# Communicate_module.net
KiCad netlist of a schematic drawn in Altium Designer
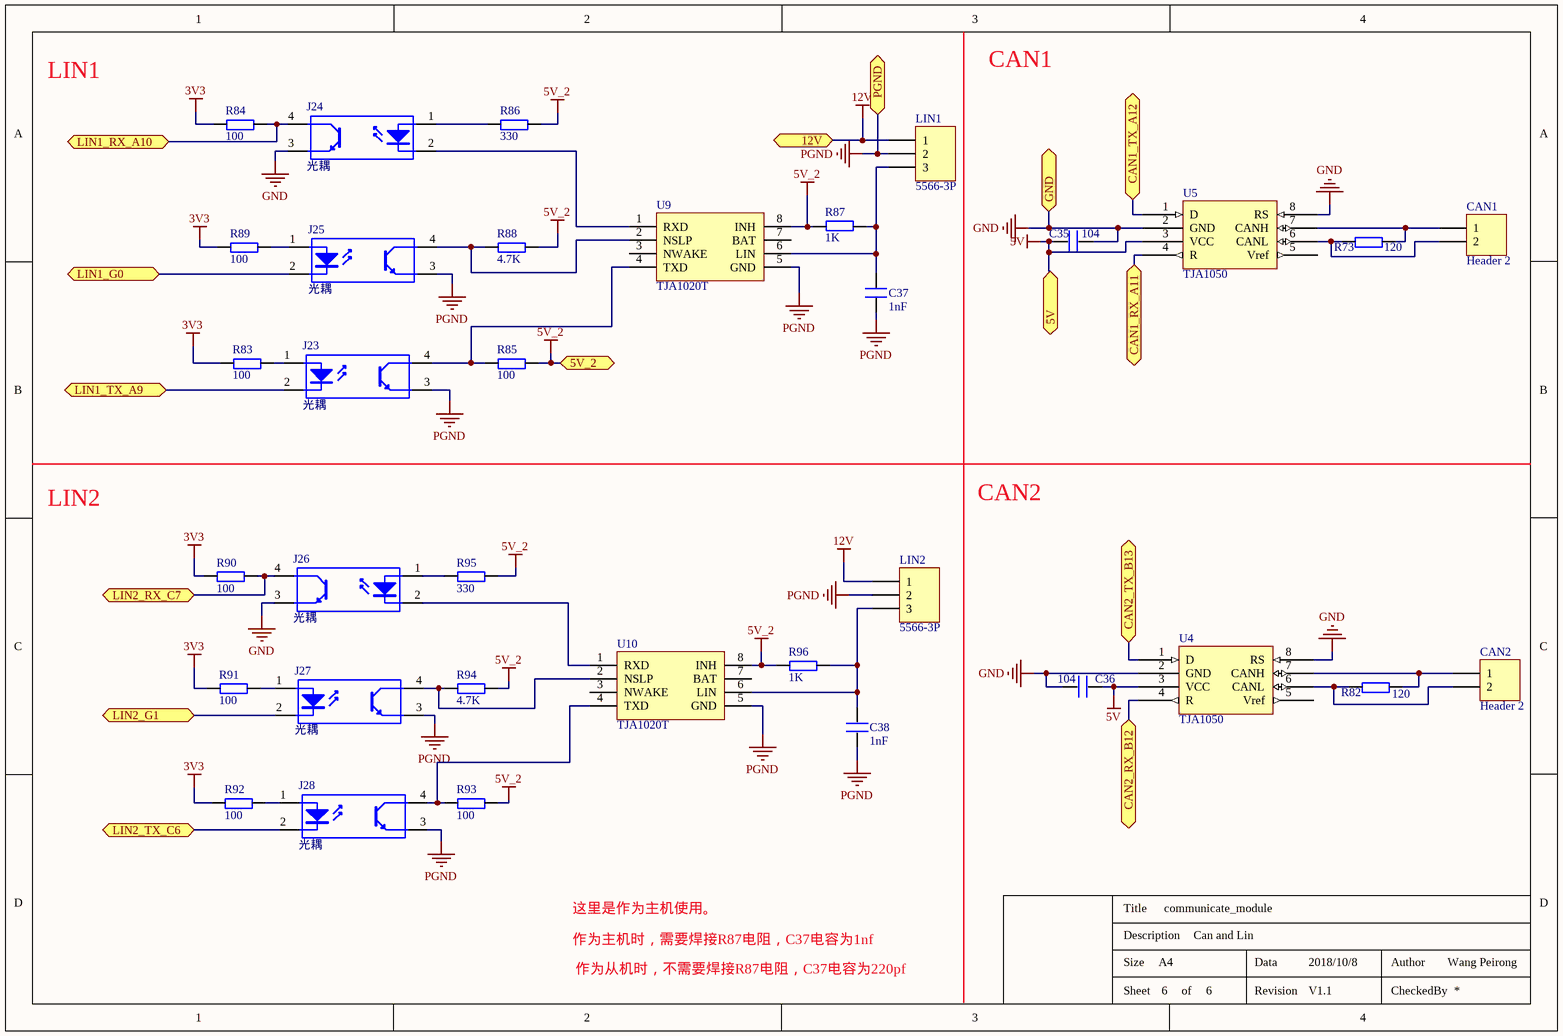
[diagram p0: Communicate_module.SchDoc]

(export (version "E")
  (design (tool "Eeschema 10.0.6"))
  (components
    (comp (ref "C35") (value "104") (footprint "0603P") (libsource (lib "阿波罗STM32F4&F7底板封装库") (part "C")))
    (comp (ref "C36") (value "104") (footprint "0603P") (libsource (lib "阿波罗STM32F4&F7底板封装库") (part "C")))
    (comp (ref "C37") (value "1nF") (footprint "0603P") (libsource (lib "阿波罗STM32F4&F7底板封装库") (part "C")))
    (comp (ref "C38") (value "1nF") (footprint "0603P") (libsource (lib "阿波罗STM32F4&F7底板封装库") (part "C")))
    (comp (ref "CAN1")
      (value "Header 2")
      (footprint "5566-2P")
      (description "Header, 2-Pin")
      (fields (field (name "PUBLISHER") "Altium Limited"))
      (libsource (lib "接插件集成库") (part "Header 2"))
    )
    (comp (ref "CAN2")
      (value "Header 2")
      (footprint "5566-2P")
      (description "Header, 2-Pin")
      (fields (field (name "PUBLISHER") "Altium Limited"))
      (libsource (lib "接插件集成库") (part "Header 2"))
    )
    (comp (ref "J23")
      (value "光耦")
      (footprint "SOP127P710X350-4N")
      (fields (field (name "PUBLISHER") "Altium Limited"))
      (libsource (lib "常用元件集成库") (part "光耦"))
    )
    (comp (ref "J24")
      (value "光耦")
      (footprint "SOP127P710X350-4N")
      (fields (field (name "PUBLISHER") "Altium Limited"))
      (libsource (lib "常用元件集成库") (part "光耦"))
    )
    (comp (ref "J25")
      (value "光耦")
      (footprint "SOP127P710X350-4N")
      (fields (field (name "PUBLISHER") "Altium Limited"))
      (libsource (lib "常用元件集成库") (part "光耦"))
    )
    (comp (ref "J26")
      (value "光耦")
      (footprint "SOP127P710X350-4N")
      (fields (field (name "PUBLISHER") "Altium Limited"))
      (libsource (lib "常用元件集成库") (part "光耦"))
    )
    (comp (ref "J27")
      (value "光耦")
      (footprint "SOP127P710X350-4N")
      (fields (field (name "PUBLISHER") "Altium Limited"))
      (libsource (lib "常用元件集成库") (part "光耦"))
    )
    (comp (ref "J28")
      (value "光耦")
      (footprint "SOP127P710X350-4N")
      (fields (field (name "PUBLISHER") "Altium Limited"))
      (libsource (lib "常用元件集成库") (part "光耦"))
    )
    (comp (ref "LIN1")
      (value "5566-3P")
      (footprint "5566-3P")
      (description "Header, 3-Pin")
      (fields (field (name "PUBLISHER") "Altium Limited"))
      (libsource (lib "接插件集成库") (part "Header 3"))
    )
    (comp (ref "LIN2")
      (value "5566-3P")
      (footprint "5566-3P")
      (description "Header, 3-Pin")
      (fields (field (name "PUBLISHER") "Altium Limited"))
      (libsource (lib "接插件集成库") (part "Header 3"))
    )
    (comp (ref "R73") (value "120") (footprint "0603P") (libsource (lib "阿波罗STM32F4&F7底板封装库") (part "R")))
    (comp (ref "R82") (value "120") (footprint "0603P") (libsource (lib "阿波罗STM32F4&F7底板封装库") (part "R")))
    (comp (ref "R83") (value "100") (footprint "0603P") (libsource (lib "阿波罗STM32F4&F7底板封装库") (part "R")))
    (comp (ref "R84") (value "100") (footprint "0603P") (libsource (lib "阿波罗STM32F4&F7底板封装库") (part "R")))
    (comp (ref "R85") (value "100") (footprint "0603P") (libsource (lib "阿波罗STM32F4&F7底板封装库") (part "R")))
    (comp (ref "R86") (value "330") (footprint "0603P") (libsource (lib "阿波罗STM32F4&F7底板封装库") (part "R")))
    (comp (ref "R87") (value "1K") (footprint "0603P") (libsource (lib "阿波罗STM32F4&F7底板封装库") (part "R")))
    (comp (ref "R88") (value "4.7K") (footprint "0603P") (libsource (lib "阿波罗STM32F4&F7底板封装库") (part "R")))
    (comp (ref "R89") (value "100") (footprint "0603P") (libsource (lib "阿波罗STM32F4&F7底板封装库") (part "R")))
    (comp (ref "R90") (value "100") (footprint "0603P") (libsource (lib "阿波罗STM32F4&F7底板封装库") (part "R")))
    (comp (ref "R91") (value "100") (footprint "0603P") (libsource (lib "阿波罗STM32F4&F7底板封装库") (part "R")))
    (comp (ref "R92") (value "100") (footprint "0603P") (libsource (lib "阿波罗STM32F4&F7底板封装库") (part "R")))
    (comp (ref "R93") (value "100") (footprint "0603P") (libsource (lib "阿波罗STM32F4&F7底板封装库") (part "R")))
    (comp (ref "R94") (value "4.7K") (footprint "0603P") (libsource (lib "阿波罗STM32F4&F7底板封装库") (part "R")))
    (comp (ref "R95") (value "330") (footprint "0603P") (libsource (lib "阿波罗STM32F4&F7底板封装库") (part "R")))
    (comp (ref "R96") (value "1K") (footprint "0603P") (libsource (lib "阿波罗STM32F4&F7底板封装库") (part "R")))
    (comp (ref "U4")
      (value "TJA1050")
      (footprint "SOP-8")
      (libsource (lib "阿波罗STM32F4&F7底板封装库") (part "SN65HVD230D"))
    )
    (comp (ref "U5")
      (value "TJA1050")
      (footprint "SOP-8")
      (libsource (lib "阿波罗STM32F4&F7底板封装库") (part "SN65HVD230D"))
    )
    (comp (ref "U9") (value "TJA1020T") (footprint "NSO8_N") (libsource (lib "IC集成库") (part "TJA1020T")))
    (comp (ref "U10") (value "TJA1020T") (footprint "NSO8_N") (libsource (lib "IC集成库") (part "TJA1020T")))
  )
  (nets
    (net (code "1") (name "/CAN1_RX_A11") (class "Default")
      (node (ref "U5") (pin "4") (pinfunction "R_4") (pintype "output"))
    )
    (net (code "2") (name "/CAN1_TX_A12") (class "Default")
      (node (ref "U5") (pin "1") (pinfunction "D_1") (pintype "input"))
    )
    (net (code "3") (name "/CAN2_RX_B12") (class "Default")
      (node (ref "U4") (pin "4") (pinfunction "R_4") (pintype "output"))
    )
    (net (code "4") (name "/CAN2_TX_B13") (class "Default")
      (node (ref "U4") (pin "1") (pinfunction "D_1") (pintype "input"))
    )
    (net (code "5") (name "/LIN1_G0") (class "Default")
      (node (ref "J25") (pin "2") (pinfunction "K_2") (pintype "passive"))
    )
    (net (code "6") (name "/LIN1_RX_A10") (class "Default")
      (node (ref "J24") (pin "4") (pinfunction "C_4") (pintype "passive"))
      (node (ref "R84") (pin "2") (pintype "passive"))
    )
    (net (code "7") (name "/LIN1_TX_A9") (class "Default")
      (node (ref "J23") (pin "2") (pinfunction "K_2") (pintype "passive"))
    )
    (net (code "8") (name "/LIN2_G1") (class "Default")
      (node (ref "J27") (pin "2") (pinfunction "K_2") (pintype "passive"))
    )
    (net (code "9") (name "/LIN2_RX_C7") (class "Default")
      (node (ref "J26") (pin "4") (pinfunction "C_4") (pintype "passive"))
      (node (ref "R90") (pin "2") (pintype "passive"))
    )
    (net (code "10") (name "/LIN2_TX_C6") (class "Default")
      (node (ref "J28") (pin "2") (pinfunction "K_2") (pintype "passive"))
    )
    (net (code "11") (name "3V3") (class "Default")
      (node (ref "R83") (pin "1") (pintype "passive"))
      (node (ref "R84") (pin "1") (pintype "passive"))
      (node (ref "R89") (pin "1") (pintype "passive"))
      (node (ref "R90") (pin "1") (pintype "passive"))
      (node (ref "R91") (pin "1") (pintype "passive"))
      (node (ref "R92") (pin "1") (pintype "passive"))
    )
    (net (code "12") (name "5V") (class "Default")
      (node (ref "C35") (pin "1") (pintype "passive"))
      (node (ref "C36") (pin "2") (pintype "passive"))
      (node (ref "U4") (pin "3") (pinfunction "VCC_3") (pintype "power_in"))
      (node (ref "U5") (pin "3") (pinfunction "VCC_3") (pintype "power_in"))
    )
    (net (code "13") (name "5V_2") (class "Default")
      (node (ref "R85") (pin "2") (pintype "passive"))
      (node (ref "R86") (pin "2") (pintype "passive"))
      (node (ref "R87") (pin "2") (pintype "passive"))
      (node (ref "R88") (pin "2") (pintype "passive"))
      (node (ref "R93") (pin "2") (pintype "passive"))
      (node (ref "R94") (pin "2") (pintype "passive"))
      (node (ref "R95") (pin "2") (pintype "passive"))
      (node (ref "R96") (pin "1") (pintype "passive"))
      (node (ref "U10") (pin "8") (pinfunction "INH_8") (pintype "passive"))
      (node (ref "U9") (pin "8") (pinfunction "INH_8") (pintype "passive"))
    )
    (net (code "14") (name "12V") (class "Default")
      (node (ref "LIN1") (pin "1") (pinfunction "1_1") (pintype "passive"))
      (node (ref "LIN2") (pin "1") (pinfunction "1_1") (pintype "passive"))
    )
    (net (code "15") (name "GND") (class "Default")
      (node (ref "C35") (pin "2") (pintype "passive"))
      (node (ref "C36") (pin "1") (pintype "passive"))
      (node (ref "J24") (pin "3") (pinfunction "E_3") (pintype "passive"))
      (node (ref "J26") (pin "3") (pinfunction "E_3") (pintype "passive"))
      (node (ref "U4") (pin "2") (pinfunction "GND_2") (pintype "power_in"))
      (node (ref "U4") (pin "8") (pinfunction "RS_8") (pintype "input"))
      (node (ref "U5") (pin "2") (pinfunction "GND_2") (pintype "power_in"))
      (node (ref "U5") (pin "8") (pinfunction "RS_8") (pintype "input"))
    )
    (net (code "16") (name "Net-(J23-A)") (class "Default")
      (node (ref "J23") (pin "1") (pinfunction "A_1") (pintype "passive"))
      (node (ref "R83") (pin "2") (pintype "passive"))
    )
    (net (code "17") (name "Net-(J23-C)") (class "Default")
      (node (ref "J23") (pin "4") (pinfunction "C_4") (pintype "passive"))
      (node (ref "R85") (pin "1") (pintype "passive"))
      (node (ref "U9") (pin "4") (pinfunction "TXD_4") (pintype "passive"))
    )
    (net (code "18") (name "Net-(J24-A)") (class "Default")
      (node (ref "J24") (pin "1") (pinfunction "A_1") (pintype "passive"))
      (node (ref "R86") (pin "1") (pintype "passive"))
    )
    (net (code "19") (name "Net-(J24-K)") (class "Default")
      (node (ref "J24") (pin "2") (pinfunction "K_2") (pintype "passive"))
      (node (ref "U9") (pin "1") (pinfunction "RXD_1") (pintype "passive"))
    )
    (net (code "20") (name "Net-(J25-A)") (class "Default")
      (node (ref "J25") (pin "1") (pinfunction "A_1") (pintype "passive"))
      (node (ref "R89") (pin "2") (pintype "passive"))
    )
    (net (code "21") (name "Net-(J25-C)") (class "Default")
      (node (ref "J25") (pin "4") (pinfunction "C_4") (pintype "passive"))
      (node (ref "R88") (pin "1") (pintype "passive"))
      (node (ref "U9") (pin "2") (pinfunction "NSLP_2") (pintype "passive"))
    )
    (net (code "22") (name "Net-(J26-A)") (class "Default")
      (node (ref "J26") (pin "1") (pinfunction "A_1") (pintype "passive"))
      (node (ref "R95") (pin "1") (pintype "passive"))
    )
    (net (code "23") (name "Net-(J26-K)") (class "Default")
      (node (ref "J26") (pin "2") (pinfunction "K_2") (pintype "passive"))
      (node (ref "U10") (pin "1") (pinfunction "RXD_1") (pintype "passive"))
    )
    (net (code "24") (name "Net-(J27-A)") (class "Default")
      (node (ref "J27") (pin "1") (pinfunction "A_1") (pintype "passive"))
      (node (ref "R91") (pin "2") (pintype "passive"))
    )
    (net (code "25") (name "Net-(J27-C)") (class "Default")
      (node (ref "J27") (pin "4") (pinfunction "C_4") (pintype "passive"))
      (node (ref "R94") (pin "1") (pintype "passive"))
      (node (ref "U10") (pin "2") (pinfunction "NSLP_2") (pintype "passive"))
    )
    (net (code "26") (name "Net-(J28-A)") (class "Default")
      (node (ref "J28") (pin "1") (pinfunction "A_1") (pintype "passive"))
      (node (ref "R92") (pin "2") (pintype "passive"))
    )
    (net (code "27") (name "Net-(J28-C)") (class "Default")
      (node (ref "J28") (pin "4") (pinfunction "C_4") (pintype "passive"))
      (node (ref "R93") (pin "1") (pintype "passive"))
      (node (ref "U10") (pin "4") (pinfunction "TXD_4") (pintype "passive"))
    )
    (net (code "28") (name "Net-(U4-CANH)") (class "Default")
      (node (ref "CAN2") (pin "1") (pinfunction "1_1") (pintype "passive"))
      (node (ref "R82") (pin "2") (pintype "passive"))
      (node (ref "U4") (pin "7") (pinfunction "CANH_7") (pintype "bidirectional"))
    )
    (net (code "29") (name "Net-(U4-CANL)") (class "Default")
      (node (ref "CAN2") (pin "2") (pinfunction "2_2") (pintype "passive"))
      (node (ref "R82") (pin "1") (pintype "passive"))
      (node (ref "U4") (pin "6") (pinfunction "CANL_6") (pintype "bidirectional"))
    )
    (net (code "30") (name "Net-(U5-CANH)") (class "Default")
      (node (ref "CAN1") (pin "1") (pinfunction "1_1") (pintype "passive"))
      (node (ref "R73") (pin "2") (pintype "passive"))
      (node (ref "U5") (pin "7") (pinfunction "CANH_7") (pintype "bidirectional"))
    )
    (net (code "31") (name "Net-(U5-CANL)") (class "Default")
      (node (ref "CAN1") (pin "2") (pinfunction "2_2") (pintype "passive"))
      (node (ref "R73") (pin "1") (pintype "passive"))
      (node (ref "U5") (pin "6") (pinfunction "CANL_6") (pintype "bidirectional"))
    )
    (net (code "32") (name "Net-(U9-LIN)") (class "Default")
      (node (ref "C37") (pin "2") (pintype "passive"))
      (node (ref "LIN1") (pin "3") (pinfunction "3_3") (pintype "passive"))
      (node (ref "R87") (pin "1") (pintype "passive"))
      (node (ref "U9") (pin "6") (pinfunction "LIN_6") (pintype "passive"))
    )
    (net (code "33") (name "Net-(U10-LIN)") (class "Default")
      (node (ref "C38") (pin "2") (pintype "passive"))
      (node (ref "LIN2") (pin "3") (pinfunction "3_3") (pintype "passive"))
      (node (ref "R96") (pin "2") (pintype "passive"))
      (node (ref "U10") (pin "6") (pinfunction "LIN_6") (pintype "passive"))
    )
    (net (code "34") (name "PGND") (class "Default")
      (node (ref "C37") (pin "1") (pintype "passive"))
      (node (ref "C38") (pin "1") (pintype "passive"))
      (node (ref "J23") (pin "3") (pinfunction "E_3") (pintype "passive"))
      (node (ref "J25") (pin "3") (pinfunction "E_3") (pintype "passive"))
      (node (ref "J27") (pin "3") (pinfunction "E_3") (pintype "passive"))
      (node (ref "J28") (pin "3") (pinfunction "E_3") (pintype "passive"))
      (node (ref "LIN1") (pin "2") (pinfunction "2_2") (pintype "passive"))
      (node (ref "LIN2") (pin "2") (pinfunction "2_2") (pintype "passive"))
      (node (ref "U10") (pin "5") (pinfunction "GND_5") (pintype "passive"))
      (node (ref "U9") (pin "5") (pinfunction "GND_5") (pintype "passive"))
    )
    (net (code "35") (name "unconnected-(U4-Vref-Pad5)") (class "Default")
      (node (ref "U4") (pin "5") (pinfunction "Vref_5") (pintype "output"))
    )
    (net (code "36") (name "unconnected-(U5-Vref-Pad5)") (class "Default")
      (node (ref "U5") (pin "5") (pinfunction "Vref_5") (pintype "output"))
    )
    (net (code "37") (name "unconnected-(U9-BAT-Pad7)") (class "Default")
      (node (ref "U9") (pin "7") (pinfunction "BAT_7") (pintype "passive"))
    )
    (net (code "38") (name "unconnected-(U9-NWAKE-Pad3)") (class "Default")
      (node (ref "U9") (pin "3") (pinfunction "NWAKE_3") (pintype "passive"))
    )
    (net (code "39") (name "unconnected-(U10-BAT-Pad7)") (class "Default")
      (node (ref "U10") (pin "7") (pinfunction "BAT_7") (pintype "passive"))
    )
    (net (code "40") (name "unconnected-(U10-NWAKE-Pad3)") (class "Default")
      (node (ref "U10") (pin "3") (pinfunction "NWAKE_3") (pintype "passive"))
    )
  )
)
